# Connector_GTX.net
KiCad netlist of a schematic drawn in Altium Designer
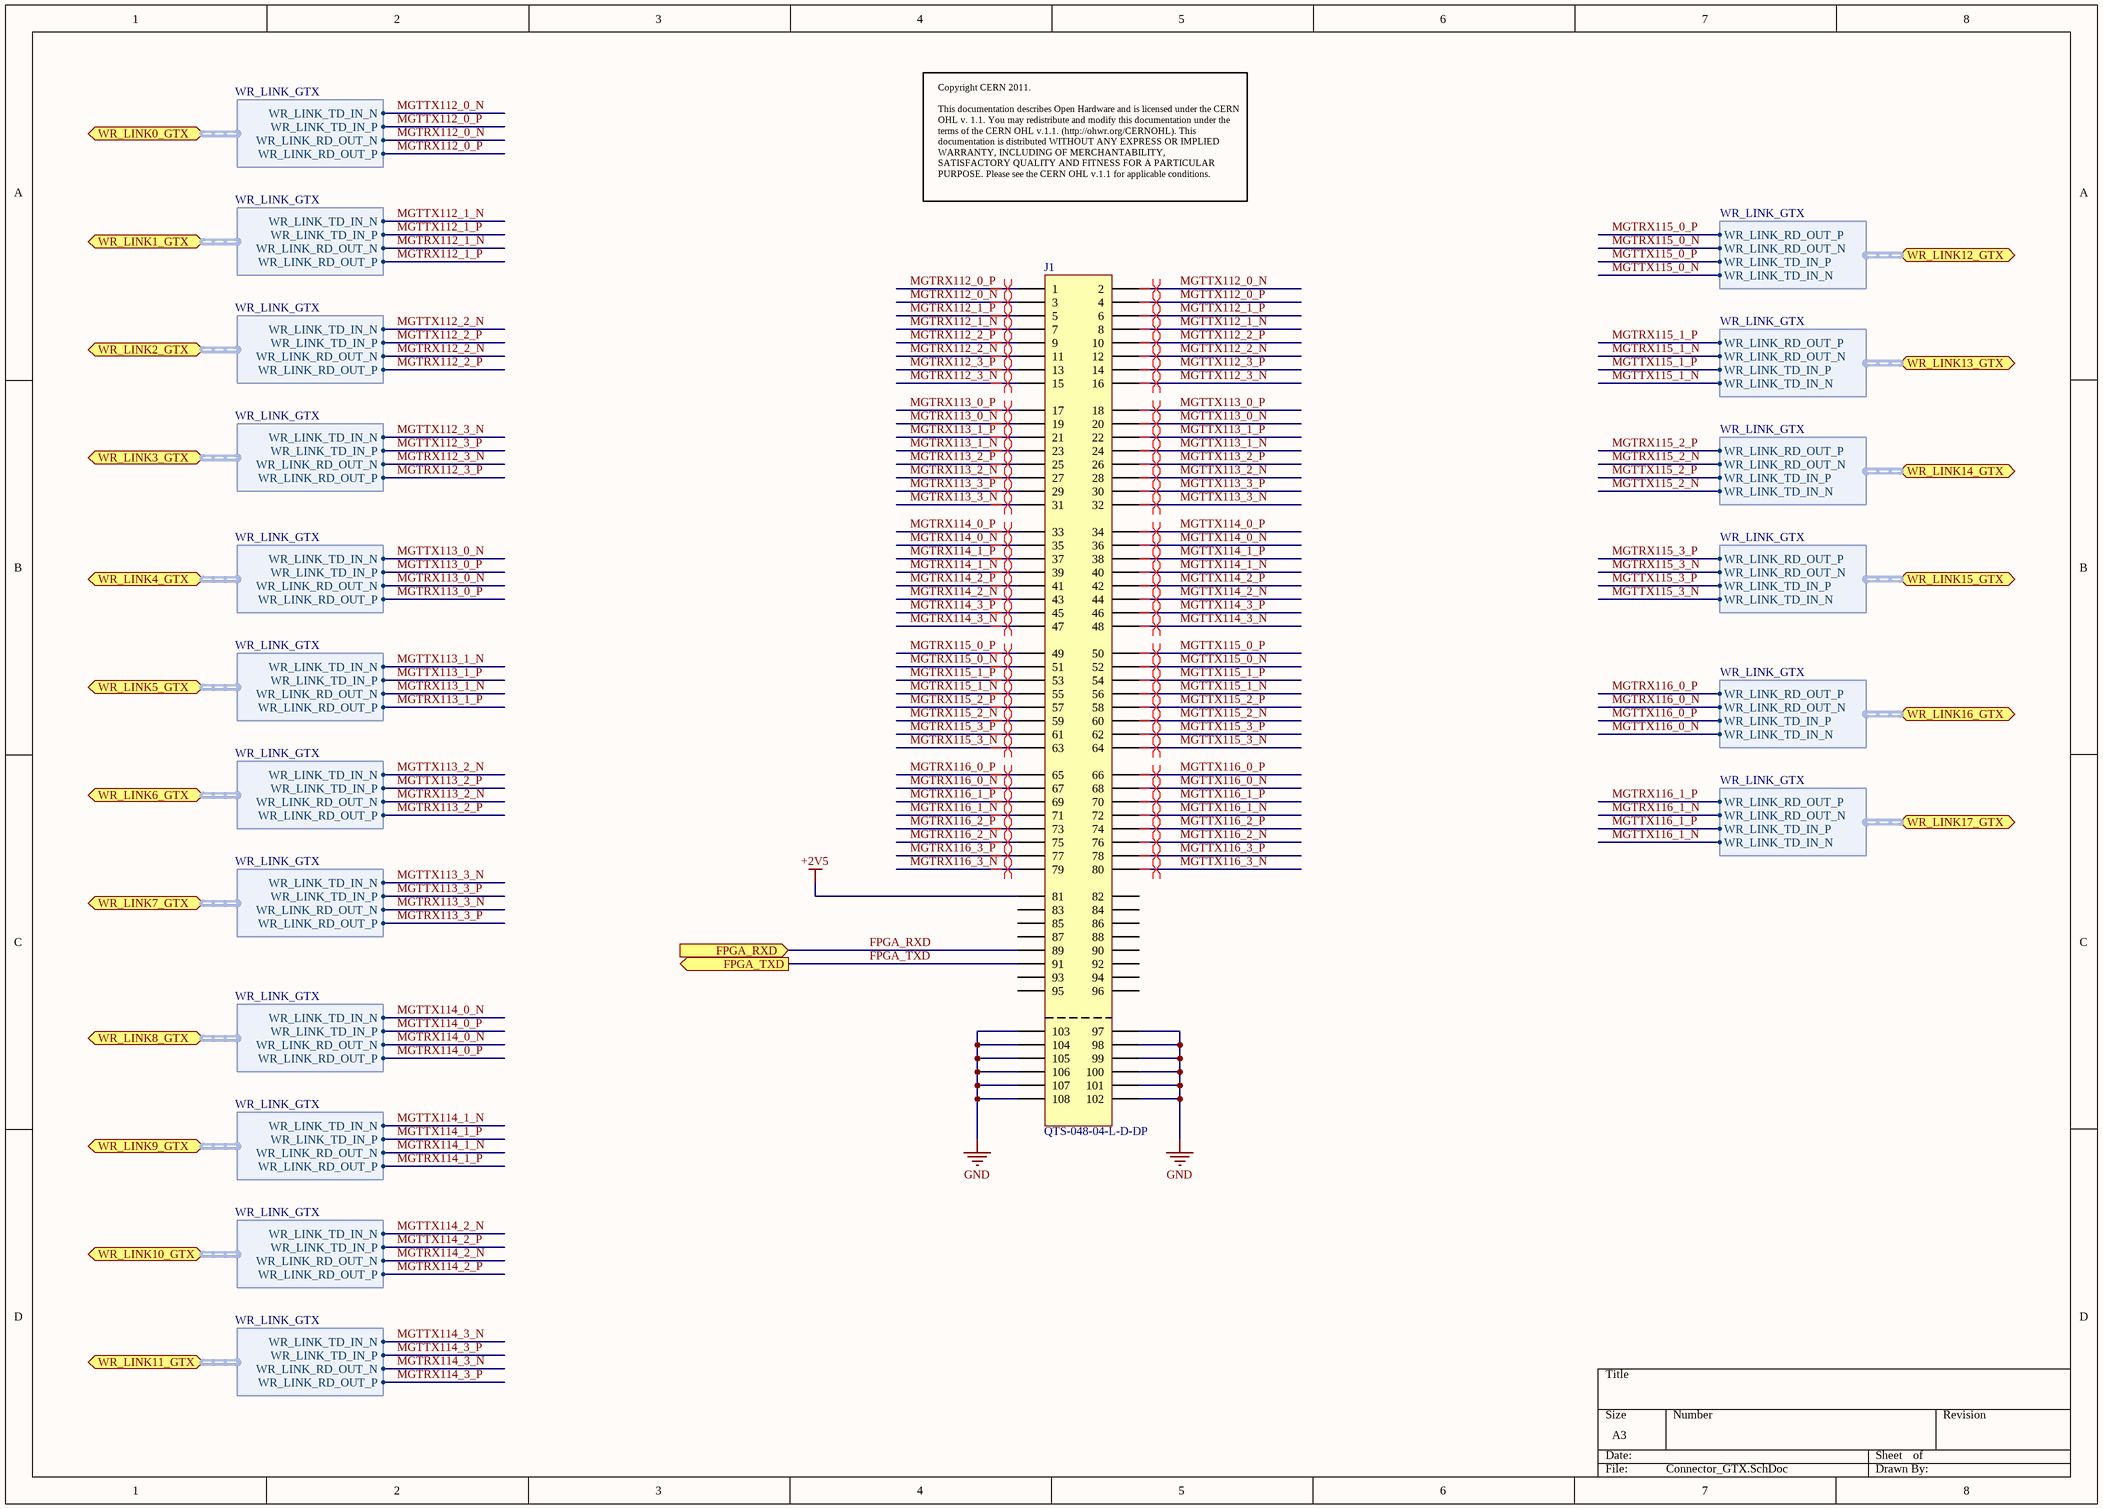
[diagram p0: Connector_GTX.SchDoc]

(export (version "E")
  (design (tool "Eeschema 10.0.6"))
  (components
    (comp (ref "J1")
      (value "QTS-048-04-L-D-DP")
      (footprint "7S_WR:QTS-048-XX-X-D-DP-A")
      (description "High Speed Ground Plane Header")
      (libsource (lib "wr_switch") (part "QTS-048-01-L-D-DP"))
    )
  )
  (nets
    (net (code "2") (name "+2V5") (class "Default")
      (node (ref "J1") (pin "81") (pinfunction "81_81") (pintype "passive"))
    )
    (net (code "3") (name "/FPGA_RXD") (class "Default")
      (node (ref "J1") (pin "89") (pinfunction "89_89") (pintype "passive"))
    )
    (net (code "4") (name "/FPGA_TXD") (class "Default")
      (node (ref "J1") (pin "91") (pinfunction "91_91") (pintype "passive"))
    )
    (net (code "5") (name "/MGTRX112_0_N") (class "Default")
      (node (ref "J1") (pin "3") (pinfunction "3_3") (pintype "passive"))
    )
    (net (code "6") (name "/MGTRX112_0_P") (class "Default")
      (node (ref "J1") (pin "1") (pinfunction "1_1") (pintype "passive"))
    )
    (net (code "7") (name "/MGTRX112_1_N") (class "Default")
      (node (ref "J1") (pin "7") (pinfunction "7_7") (pintype "passive"))
    )
    (net (code "8") (name "/MGTRX112_1_P") (class "Default")
      (node (ref "J1") (pin "5") (pinfunction "5_5") (pintype "passive"))
    )
    (net (code "9") (name "/MGTRX112_2_N") (class "Default")
      (node (ref "J1") (pin "11") (pinfunction "11_11") (pintype "passive"))
    )
    (net (code "10") (name "/MGTRX112_2_P") (class "Default")
      (node (ref "J1") (pin "9") (pinfunction "9_9") (pintype "passive"))
    )
    (net (code "11") (name "/MGTRX112_3_N") (class "Default")
      (node (ref "J1") (pin "15") (pinfunction "15_15") (pintype "passive"))
    )
    (net (code "12") (name "/MGTRX112_3_P") (class "Default")
      (node (ref "J1") (pin "13") (pinfunction "13_13") (pintype "passive"))
    )
    (net (code "13") (name "/MGTRX113_0_N") (class "Default")
      (node (ref "J1") (pin "19") (pinfunction "19_19") (pintype "passive"))
    )
    (net (code "14") (name "/MGTRX113_0_P") (class "Default")
      (node (ref "J1") (pin "17") (pinfunction "17_17") (pintype "passive"))
    )
    (net (code "15") (name "/MGTRX113_1_N") (class "Default")
      (node (ref "J1") (pin "23") (pinfunction "23_23") (pintype "passive"))
    )
    (net (code "16") (name "/MGTRX113_1_P") (class "Default")
      (node (ref "J1") (pin "21") (pinfunction "21_21") (pintype "passive"))
    )
    (net (code "17") (name "/MGTRX113_2_N") (class "Default")
      (node (ref "J1") (pin "27") (pinfunction "27_27") (pintype "passive"))
    )
    (net (code "18") (name "/MGTRX113_2_P") (class "Default")
      (node (ref "J1") (pin "25") (pinfunction "25_25") (pintype "passive"))
    )
    (net (code "19") (name "/MGTRX113_3_N") (class "Default")
      (node (ref "J1") (pin "31") (pinfunction "31_31") (pintype "passive"))
    )
    (net (code "20") (name "/MGTRX113_3_P") (class "Default")
      (node (ref "J1") (pin "29") (pinfunction "29_29") (pintype "passive"))
    )
    (net (code "21") (name "/MGTRX114_0_N") (class "Default")
      (node (ref "J1") (pin "35") (pinfunction "35_35") (pintype "passive"))
    )
    (net (code "22") (name "/MGTRX114_0_P") (class "Default")
      (node (ref "J1") (pin "33") (pinfunction "33_33") (pintype "passive"))
    )
    (net (code "23") (name "/MGTRX114_1_N") (class "Default")
      (node (ref "J1") (pin "39") (pinfunction "39_39") (pintype "passive"))
    )
    (net (code "24") (name "/MGTRX114_1_P") (class "Default")
      (node (ref "J1") (pin "37") (pinfunction "37_37") (pintype "passive"))
    )
    (net (code "25") (name "/MGTRX114_2_N") (class "Default")
      (node (ref "J1") (pin "43") (pinfunction "43_43") (pintype "passive"))
    )
    (net (code "26") (name "/MGTRX114_2_P") (class "Default")
      (node (ref "J1") (pin "41") (pinfunction "41_41") (pintype "passive"))
    )
    (net (code "27") (name "/MGTRX114_3_N") (class "Default")
      (node (ref "J1") (pin "47") (pinfunction "47_47") (pintype "passive"))
    )
    (net (code "28") (name "/MGTRX114_3_P") (class "Default")
      (node (ref "J1") (pin "45") (pinfunction "45_45") (pintype "passive"))
    )
    (net (code "29") (name "/MGTRX115_0_N") (class "Default")
      (node (ref "J1") (pin "51") (pinfunction "51_51") (pintype "passive"))
    )
    (net (code "30") (name "/MGTRX115_0_P") (class "Default")
      (node (ref "J1") (pin "49") (pinfunction "49_49") (pintype "passive"))
    )
    (net (code "31") (name "/MGTRX115_1_N") (class "Default")
      (node (ref "J1") (pin "55") (pinfunction "55_55") (pintype "passive"))
    )
    (net (code "32") (name "/MGTRX115_1_P") (class "Default")
      (node (ref "J1") (pin "53") (pinfunction "53_53") (pintype "passive"))
    )
    (net (code "33") (name "/MGTRX115_2_N") (class "Default")
      (node (ref "J1") (pin "59") (pinfunction "59_59") (pintype "passive"))
    )
    (net (code "34") (name "/MGTRX115_2_P") (class "Default")
      (node (ref "J1") (pin "57") (pinfunction "57_57") (pintype "passive"))
    )
    (net (code "35") (name "/MGTRX115_3_N") (class "Default")
      (node (ref "J1") (pin "63") (pinfunction "63_63") (pintype "passive"))
    )
    (net (code "36") (name "/MGTRX115_3_P") (class "Default")
      (node (ref "J1") (pin "61") (pinfunction "61_61") (pintype "passive"))
    )
    (net (code "37") (name "/MGTRX116_0_N") (class "Default")
      (node (ref "J1") (pin "67") (pinfunction "67_67") (pintype "passive"))
    )
    (net (code "38") (name "/MGTRX116_0_P") (class "Default")
      (node (ref "J1") (pin "65") (pinfunction "65_65") (pintype "passive"))
    )
    (net (code "39") (name "/MGTRX116_1_N") (class "Default")
      (node (ref "J1") (pin "71") (pinfunction "71_71") (pintype "passive"))
    )
    (net (code "40") (name "/MGTRX116_1_P") (class "Default")
      (node (ref "J1") (pin "69") (pinfunction "69_69") (pintype "passive"))
    )
    (net (code "41") (name "/MGTRX116_2_N") (class "Default")
      (node (ref "J1") (pin "75") (pinfunction "75_75") (pintype "passive"))
    )
    (net (code "42") (name "/MGTRX116_2_P") (class "Default")
      (node (ref "J1") (pin "73") (pinfunction "73_73") (pintype "passive"))
    )
    (net (code "43") (name "/MGTRX116_3_N") (class "Default")
      (node (ref "J1") (pin "79") (pinfunction "79_79") (pintype "passive"))
    )
    (net (code "44") (name "/MGTRX116_3_P") (class "Default")
      (node (ref "J1") (pin "77") (pinfunction "77_77") (pintype "passive"))
    )
    (net (code "45") (name "/MGTTX112_0_N") (class "Default")
      (node (ref "J1") (pin "2") (pinfunction "2_2") (pintype "passive"))
    )
    (net (code "46") (name "/MGTTX112_0_P") (class "Default")
      (node (ref "J1") (pin "4") (pinfunction "4_4") (pintype "passive"))
    )
    (net (code "47") (name "/MGTTX112_1_N") (class "Default")
      (node (ref "J1") (pin "8") (pinfunction "8_8") (pintype "passive"))
    )
    (net (code "48") (name "/MGTTX112_1_P") (class "Default")
      (node (ref "J1") (pin "6") (pinfunction "6_6") (pintype "passive"))
    )
    (net (code "49") (name "/MGTTX112_2_N") (class "Default")
      (node (ref "J1") (pin "12") (pinfunction "12_12") (pintype "passive"))
    )
    (net (code "50") (name "/MGTTX112_2_P") (class "Default")
      (node (ref "J1") (pin "10") (pinfunction "10_10") (pintype "passive"))
    )
    (net (code "51") (name "/MGTTX112_3_N") (class "Default")
      (node (ref "J1") (pin "16") (pinfunction "16_16") (pintype "passive"))
    )
    (net (code "52") (name "/MGTTX112_3_P") (class "Default")
      (node (ref "J1") (pin "14") (pinfunction "14_14") (pintype "passive"))
    )
    (net (code "53") (name "/MGTTX113_0_N") (class "Default")
      (node (ref "J1") (pin "20") (pinfunction "20_20") (pintype "passive"))
    )
    (net (code "54") (name "/MGTTX113_0_P") (class "Default")
      (node (ref "J1") (pin "18") (pinfunction "18_18") (pintype "passive"))
    )
    (net (code "55") (name "/MGTTX113_1_N") (class "Default")
      (node (ref "J1") (pin "24") (pinfunction "24_24") (pintype "passive"))
    )
    (net (code "56") (name "/MGTTX113_1_P") (class "Default")
      (node (ref "J1") (pin "22") (pinfunction "22_22") (pintype "passive"))
    )
    (net (code "57") (name "/MGTTX113_2_N") (class "Default")
      (node (ref "J1") (pin "28") (pinfunction "28_28") (pintype "passive"))
    )
    (net (code "58") (name "/MGTTX113_2_P") (class "Default")
      (node (ref "J1") (pin "26") (pinfunction "26_26") (pintype "passive"))
    )
    (net (code "59") (name "/MGTTX113_3_N") (class "Default")
      (node (ref "J1") (pin "32") (pinfunction "32_32") (pintype "passive"))
    )
    (net (code "60") (name "/MGTTX113_3_P") (class "Default")
      (node (ref "J1") (pin "30") (pinfunction "30_30") (pintype "passive"))
    )
    (net (code "61") (name "/MGTTX114_0_N") (class "Default")
      (node (ref "J1") (pin "36") (pinfunction "36_36") (pintype "passive"))
    )
    (net (code "62") (name "/MGTTX114_0_P") (class "Default")
      (node (ref "J1") (pin "34") (pinfunction "34_34") (pintype "passive"))
    )
    (net (code "63") (name "/MGTTX114_1_N") (class "Default")
      (node (ref "J1") (pin "40") (pinfunction "40_40") (pintype "passive"))
    )
    (net (code "64") (name "/MGTTX114_1_P") (class "Default")
      (node (ref "J1") (pin "38") (pinfunction "38_38") (pintype "passive"))
    )
    (net (code "65") (name "/MGTTX114_2_N") (class "Default")
      (node (ref "J1") (pin "44") (pinfunction "44_44") (pintype "passive"))
    )
    (net (code "66") (name "/MGTTX114_2_P") (class "Default")
      (node (ref "J1") (pin "42") (pinfunction "42_42") (pintype "passive"))
    )
    (net (code "67") (name "/MGTTX114_3_N") (class "Default")
      (node (ref "J1") (pin "48") (pinfunction "48_48") (pintype "passive"))
    )
    (net (code "68") (name "/MGTTX114_3_P") (class "Default")
      (node (ref "J1") (pin "46") (pinfunction "46_46") (pintype "passive"))
    )
    (net (code "69") (name "/MGTTX115_0_N") (class "Default")
      (node (ref "J1") (pin "52") (pinfunction "52_52") (pintype "passive"))
    )
    (net (code "70") (name "/MGTTX115_0_P") (class "Default")
      (node (ref "J1") (pin "50") (pinfunction "50_50") (pintype "passive"))
    )
    (net (code "71") (name "/MGTTX115_1_N") (class "Default")
      (node (ref "J1") (pin "56") (pinfunction "56_56") (pintype "passive"))
    )
    (net (code "72") (name "/MGTTX115_1_P") (class "Default")
      (node (ref "J1") (pin "54") (pinfunction "54_54") (pintype "passive"))
    )
    (net (code "73") (name "/MGTTX115_2_N") (class "Default")
      (node (ref "J1") (pin "60") (pinfunction "60_60") (pintype "passive"))
    )
    (net (code "74") (name "/MGTTX115_2_P") (class "Default")
      (node (ref "J1") (pin "58") (pinfunction "58_58") (pintype "passive"))
    )
    (net (code "75") (name "/MGTTX115_3_N") (class "Default")
      (node (ref "J1") (pin "64") (pinfunction "64_64") (pintype "passive"))
    )
    (net (code "76") (name "/MGTTX115_3_P") (class "Default")
      (node (ref "J1") (pin "62") (pinfunction "62_62") (pintype "passive"))
    )
    (net (code "77") (name "/MGTTX116_0_N") (class "Default")
      (node (ref "J1") (pin "68") (pinfunction "68_68") (pintype "passive"))
    )
    (net (code "78") (name "/MGTTX116_0_P") (class "Default")
      (node (ref "J1") (pin "66") (pinfunction "66_66") (pintype "passive"))
    )
    (net (code "79") (name "/MGTTX116_1_N") (class "Default")
      (node (ref "J1") (pin "72") (pinfunction "72_72") (pintype "passive"))
    )
    (net (code "80") (name "/MGTTX116_1_P") (class "Default")
      (node (ref "J1") (pin "70") (pinfunction "70_70") (pintype "passive"))
    )
    (net (code "81") (name "/MGTTX116_2_N") (class "Default")
      (node (ref "J1") (pin "76") (pinfunction "76_76") (pintype "passive"))
    )
    (net (code "82") (name "/MGTTX116_2_P") (class "Default")
      (node (ref "J1") (pin "74") (pinfunction "74_74") (pintype "passive"))
    )
    (net (code "83") (name "/MGTTX116_3_N") (class "Default")
      (node (ref "J1") (pin "80") (pinfunction "80_80") (pintype "passive"))
    )
    (net (code "84") (name "/MGTTX116_3_P") (class "Default")
      (node (ref "J1") (pin "78") (pinfunction "78_78") (pintype "passive"))
    )
    (net (code "86") (name "GND") (class "Default")
      (node (ref "J1") (pin "100") (pinfunction "100_100") (pintype "passive"))
      (node (ref "J1") (pin "101") (pinfunction "101_101") (pintype "passive"))
      (node (ref "J1") (pin "102") (pinfunction "102_102") (pintype "passive"))
      (node (ref "J1") (pin "103") (pinfunction "103_103") (pintype "passive"))
      (node (ref "J1") (pin "104") (pinfunction "104_104") (pintype "passive"))
      (node (ref "J1") (pin "105") (pinfunction "105_105") (pintype "passive"))
      (node (ref "J1") (pin "106") (pinfunction "106_106") (pintype "passive"))
      (node (ref "J1") (pin "107") (pinfunction "107_107") (pintype "passive"))
      (node (ref "J1") (pin "108") (pinfunction "108_108") (pintype "passive"))
      (node (ref "J1") (pin "97") (pinfunction "97_97") (pintype "passive"))
      (node (ref "J1") (pin "98") (pinfunction "98_98") (pintype "passive"))
      (node (ref "J1") (pin "99") (pinfunction "99_99") (pintype "passive"))
    )
    (net (code "87") (name "unconnected-(J1-Pad82)") (class "Default")
      (node (ref "J1") (pin "82") (pinfunction "82_82") (pintype "passive"))
    )
    (net (code "88") (name "unconnected-(J1-Pad83)") (class "Default")
      (node (ref "J1") (pin "83") (pinfunction "83_83") (pintype "passive"))
    )
    (net (code "89") (name "unconnected-(J1-Pad84)") (class "Default")
      (node (ref "J1") (pin "84") (pinfunction "84_84") (pintype "passive"))
    )
    (net (code "90") (name "unconnected-(J1-Pad85)") (class "Default")
      (node (ref "J1") (pin "85") (pinfunction "85_85") (pintype "passive"))
    )
    (net (code "91") (name "unconnected-(J1-Pad86)") (class "Default")
      (node (ref "J1") (pin "86") (pinfunction "86_86") (pintype "passive"))
    )
    (net (code "92") (name "unconnected-(J1-Pad87)") (class "Default")
      (node (ref "J1") (pin "87") (pinfunction "87_87") (pintype "passive"))
    )
    (net (code "93") (name "unconnected-(J1-Pad88)") (class "Default")
      (node (ref "J1") (pin "88") (pinfunction "88_88") (pintype "passive"))
    )
    (net (code "94") (name "unconnected-(J1-Pad90)") (class "Default")
      (node (ref "J1") (pin "90") (pinfunction "90_90") (pintype "passive"))
    )
    (net (code "95") (name "unconnected-(J1-Pad92)") (class "Default")
      (node (ref "J1") (pin "92") (pinfunction "92_92") (pintype "passive"))
    )
    (net (code "96") (name "unconnected-(J1-Pad93)") (class "Default")
      (node (ref "J1") (pin "93") (pinfunction "93_93") (pintype "passive"))
    )
    (net (code "97") (name "unconnected-(J1-Pad94)") (class "Default")
      (node (ref "J1") (pin "94") (pinfunction "94_94") (pintype "passive"))
    )
    (net (code "98") (name "unconnected-(J1-Pad95)") (class "Default")
      (node (ref "J1") (pin "95") (pinfunction "95_95") (pintype "passive"))
    )
    (net (code "99") (name "unconnected-(J1-Pad96)") (class "Default")
      (node (ref "J1") (pin "96") (pinfunction "96_96") (pintype "passive"))
    )
  )
)
